# Sensors.net
KiCad netlist of a schematic drawn in Altium Designer
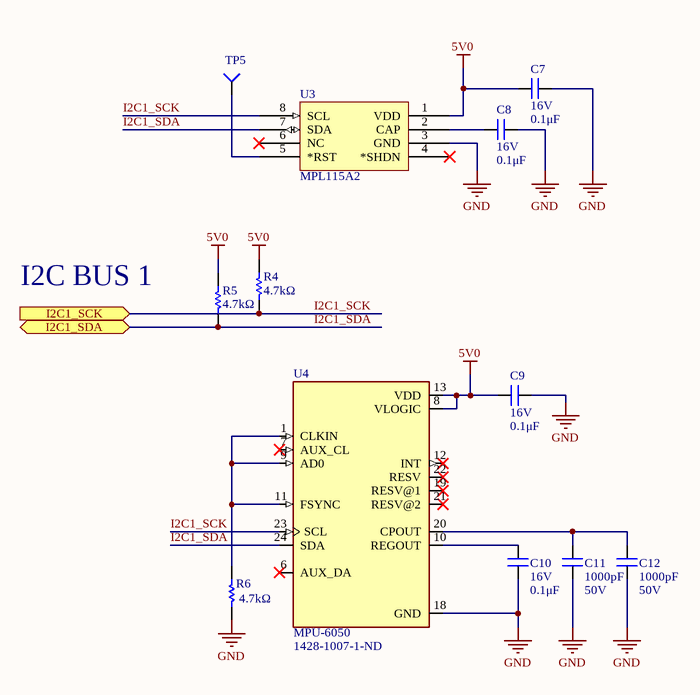
[diagram p0: Sensors.SchDoc]

(export (version "E")
  (design (tool "Eeschema 10.0.6"))
  (components
    (comp (ref "C7")
      (value "0.1μF")
      (footprint "CAP0603")
      (description "CAP CER 0.1UF 16V X7R 0603")
      (fields (field (name "VOLTAGE RATING") "16V") (field (name "Comment") "CAP_0.1uF_16V_0603"))
      (libsource (lib "SKALE_LIB") (part "CAP_0.1uF_16V_0603"))
    )
    (comp (ref "C8")
      (value "0.1μF")
      (footprint "CAP0603")
      (description "CAP CER 0.1UF 16V X7R 0603")
      (fields (field (name "VOLTAGE RATING") "16V") (field (name "Comment") "CAP_0.1uF_16V_0603"))
      (libsource (lib "SKALE_LIB") (part "CAP_0.1uF_16V_0603"))
    )
    (comp (ref "C9")
      (value "0.1μF")
      (footprint "CAP0603")
      (description "CAP CER 0.1UF 16V X7R 0603")
      (fields (field (name "VOLTAGE RATING") "16V") (field (name "Comment") "CAP_0.1uF_16V_0603"))
      (libsource (lib "SKALE_LIB") (part "CAP_0.1uF_16V_0603"))
    )
    (comp (ref "C10")
      (value "0.1μF")
      (footprint "CAP0603")
      (description "CAP CER 0.1UF 16V X7R 0603")
      (fields (field (name "VOLTAGE RATING") "16V") (field (name "Comment") "CAP_0.1uF_16V_0603"))
      (libsource (lib "SKALE_LIB") (part "CAP_0.1uF_16V_0603"))
    )
    (comp (ref "C11")
      (value "1000pF")
      (footprint "CAP0805")
      (description "CAP CER 1000pF 50V X7R 0805")
      (fields (field (name "VOLTAGE RATING") "50V") (field (name "Comment") "CAP_1000pF_50V_0805"))
      (libsource (lib "SKALE_LIB") (part "CAP_1000pF_50V_0805"))
    )
    (comp (ref "C12")
      (value "1000pF")
      (footprint "CAP0805")
      (description "CAP CER 1000pF 50V X7R 0805")
      (fields (field (name "VOLTAGE RATING") "50V") (field (name "Comment") "CAP_1000pF_50V_0805"))
      (libsource (lib "SKALE_LIB") (part "CAP_1000pF_50V_0805"))
    )
    (comp (ref "R4")
      (value "4.7kΩ")
      (footprint "RES0603")
      (description "RES 4.7K OHM 5% 1/10W 0603")
      (fields (field (name "Comment") "RES_4.7kΩ_0603"))
      (libsource (lib "SKALE_LIB") (part "RES_4.7kΩ_0603_5%"))
    )
    (comp (ref "R5")
      (value "4.7kΩ")
      (footprint "RES0603")
      (description "RES 4.7K OHM 5% 1/10W 0603")
      (fields (field (name "Comment") "RES_4.7kΩ_0603"))
      (libsource (lib "SKALE_LIB") (part "RES_4.7kΩ_0603_5%"))
    )
    (comp (ref "R6")
      (value "4.7kΩ")
      (footprint "RES0603")
      (description "RES 4.7K OHM 5% 1/10W 0603")
      (fields (field (name "Comment") "RES_4.7kΩ_0603"))
      (libsource (lib "SKALE_LIB") (part "RES_4.7kΩ_0603_5%"))
    )
    (comp (ref "TP5")
      (value "TESTPT")
      (footprint "TESTPT SQUARE")
      (libsource (lib "SKALE_LIB") (part "TESTPT SQUARE"))
    )
    (comp (ref "U3")
      (value "MPL115A2")
      (footprint "LGA8 - MPL115A2")
      (description "Absolute, 7.25Psi Min, 16.67Psi Max, Rectangular, Surface Mount")
      (fields (field (name "MF") "NXP USA") (field (name "MANUFACTURER") "NXP Freescale"))
      (libsource (lib "SKALE_LIB") (part "MPL115A2"))
    )
    (comp (ref "U4")
      (value "MPU-6050")
      (footprint "SKALE_LIB:QFN50P400X400X95-24N")
      (description "Analog Circuit, 1 Func, CMOS")
      (fields (field (name "MF") "TDK InvenSense") (field (name "SUPPLIER PART NUMBER 1") "1428-1007-1-ND"))
      (libsource (lib "SKALE_LIB") (part "MPU-6050"))
    )
  )
  (nets
    (net (code "1") (name "/I2C1_SCK") (class "Default")
      (node (ref "R4") (pin "2") (pinfunction "2_2") (pintype "passive"))
      (node (ref "U3") (pin "8") (pinfunction "SCL_8") (pintype "input"))
      (node (ref "U4") (pin "23") (pinfunction "SCL_23") (pintype "input"))
    )
    (net (code "2") (name "/I2C1_SDA") (class "Default")
      (node (ref "R5") (pin "2") (pinfunction "2_2") (pintype "passive"))
      (node (ref "U3") (pin "7") (pinfunction "SDA_7") (pintype "bidirectional"))
      (node (ref "U4") (pin "24") (pinfunction "SDA_24") (pintype "bidirectional"))
    )
    (net (code "3") (name "5V0") (class "Default")
      (node (ref "C7") (pin "2") (pinfunction "2_2") (pintype "passive"))
      (node (ref "C9") (pin "2") (pinfunction "2_2") (pintype "passive"))
      (node (ref "R4") (pin "1") (pinfunction "1_1") (pintype "passive"))
      (node (ref "R5") (pin "1") (pinfunction "1_1") (pintype "passive"))
      (node (ref "U3") (pin "1") (pinfunction "VDD_1") (pintype "power_in"))
      (node (ref "U4") (pin "13") (pinfunction "VDD_13") (pintype "power_in"))
      (node (ref "U4") (pin "8") (pinfunction "VLOGIC_8") (pintype "power_in"))
    )
    (net (code "4") (name "GND") (class "Default")
      (node (ref "C10") (pin "1") (pinfunction "1_1") (pintype "passive"))
      (node (ref "C11") (pin "1") (pinfunction "1_1") (pintype "passive"))
      (node (ref "C12") (pin "1") (pinfunction "1_1") (pintype "passive"))
      (node (ref "C7") (pin "1") (pinfunction "1_1") (pintype "passive"))
      (node (ref "C8") (pin "1") (pinfunction "1_1") (pintype "passive"))
      (node (ref "C9") (pin "1") (pinfunction "1_1") (pintype "passive"))
      (node (ref "R6") (pin "2") (pinfunction "2_2") (pintype "passive"))
      (node (ref "U3") (pin "3") (pinfunction "GND_3") (pintype "power_in"))
      (node (ref "U4") (pin "18") (pinfunction "GND_18") (pintype "power_in"))
    )
    (net (code "5") (name "Net-(TP5-=value)") (class "Default")
      (node (ref "TP5") (pin "1") (pinfunction "=value_1") (pintype "passive"))
      (node (ref "U3") (pin "5") (pinfunction "*RST_5") (pintype "passive"))
    )
    (net (code "6") (name "Net-(U3-CAP)") (class "Default")
      (node (ref "C8") (pin "2") (pinfunction "2_2") (pintype "passive"))
      (node (ref "U3") (pin "2") (pinfunction "CAP_2") (pintype "passive"))
    )
    (net (code "7") (name "Net-(U4-AD0)") (class "Default")
      (node (ref "R6") (pin "1") (pinfunction "1_1") (pintype "passive"))
      (node (ref "U4") (pin "1") (pinfunction "CLKIN_1") (pintype "input"))
      (node (ref "U4") (pin "11") (pinfunction "FSYNC_11") (pintype "input"))
      (node (ref "U4") (pin "9") (pinfunction "AD0_9") (pintype "input"))
    )
    (net (code "8") (name "Net-(U4-CPOUT)") (class "Default")
      (node (ref "C11") (pin "2") (pinfunction "2_2") (pintype "passive"))
      (node (ref "C12") (pin "2") (pinfunction "2_2") (pintype "passive"))
      (node (ref "U4") (pin "20") (pinfunction "CPOUT_20") (pintype "passive"))
    )
    (net (code "9") (name "Net-(U4-REGOUT)") (class "Default")
      (node (ref "C10") (pin "2") (pinfunction "2_2") (pintype "passive"))
      (node (ref "U4") (pin "10") (pinfunction "REGOUT_10") (pintype "passive"))
    )
    (net (code "10") (name "unconnected-(U3-*SHDN-Pad4)") (class "Default")
      (node (ref "U3") (pin "4") (pinfunction "*SHDN_4") (pintype "passive+no_connect"))
    )
    (net (code "11") (name "unconnected-(U3-NC-Pad6)") (class "Default")
      (node (ref "U3") (pin "6") (pinfunction "NC_6") (pintype "passive+no_connect"))
    )
    (net (code "12") (name "unconnected-(U4-AUX_CL-Pad7)") (class "Default")
      (node (ref "U4") (pin "7") (pinfunction "AUX_CL_7") (pintype "input+no_connect"))
    )
    (net (code "13") (name "unconnected-(U4-AUX_DA-Pad6)") (class "Default")
      (node (ref "U4") (pin "6") (pinfunction "AUX_DA_6") (pintype "bidirectional+no_connect"))
    )
    (net (code "14") (name "unconnected-(U4-INT-Pad12)") (class "Default")
      (node (ref "U4") (pin "12") (pinfunction "INT_12") (pintype "output+no_connect"))
    )
    (net (code "15") (name "unconnected-(U4-RESV-Pad22)") (class "Default")
      (node (ref "U4") (pin "22") (pinfunction "RESV_22") (pintype "passive+no_connect"))
    )
    (net (code "16") (name "unconnected-(U4-RESV@1-Pad19)") (class "Default")
      (node (ref "U4") (pin "19") (pinfunction "RESV@1_19") (pintype "passive+no_connect"))
    )
    (net (code "17") (name "unconnected-(U4-RESV@2-Pad21)") (class "Default")
      (node (ref "U4") (pin "21") (pinfunction "RESV@2_21") (pintype "passive+no_connect"))
    )
  )
)
